# Flash_Memory.net
KiCad netlist of a schematic drawn in Altium Designer
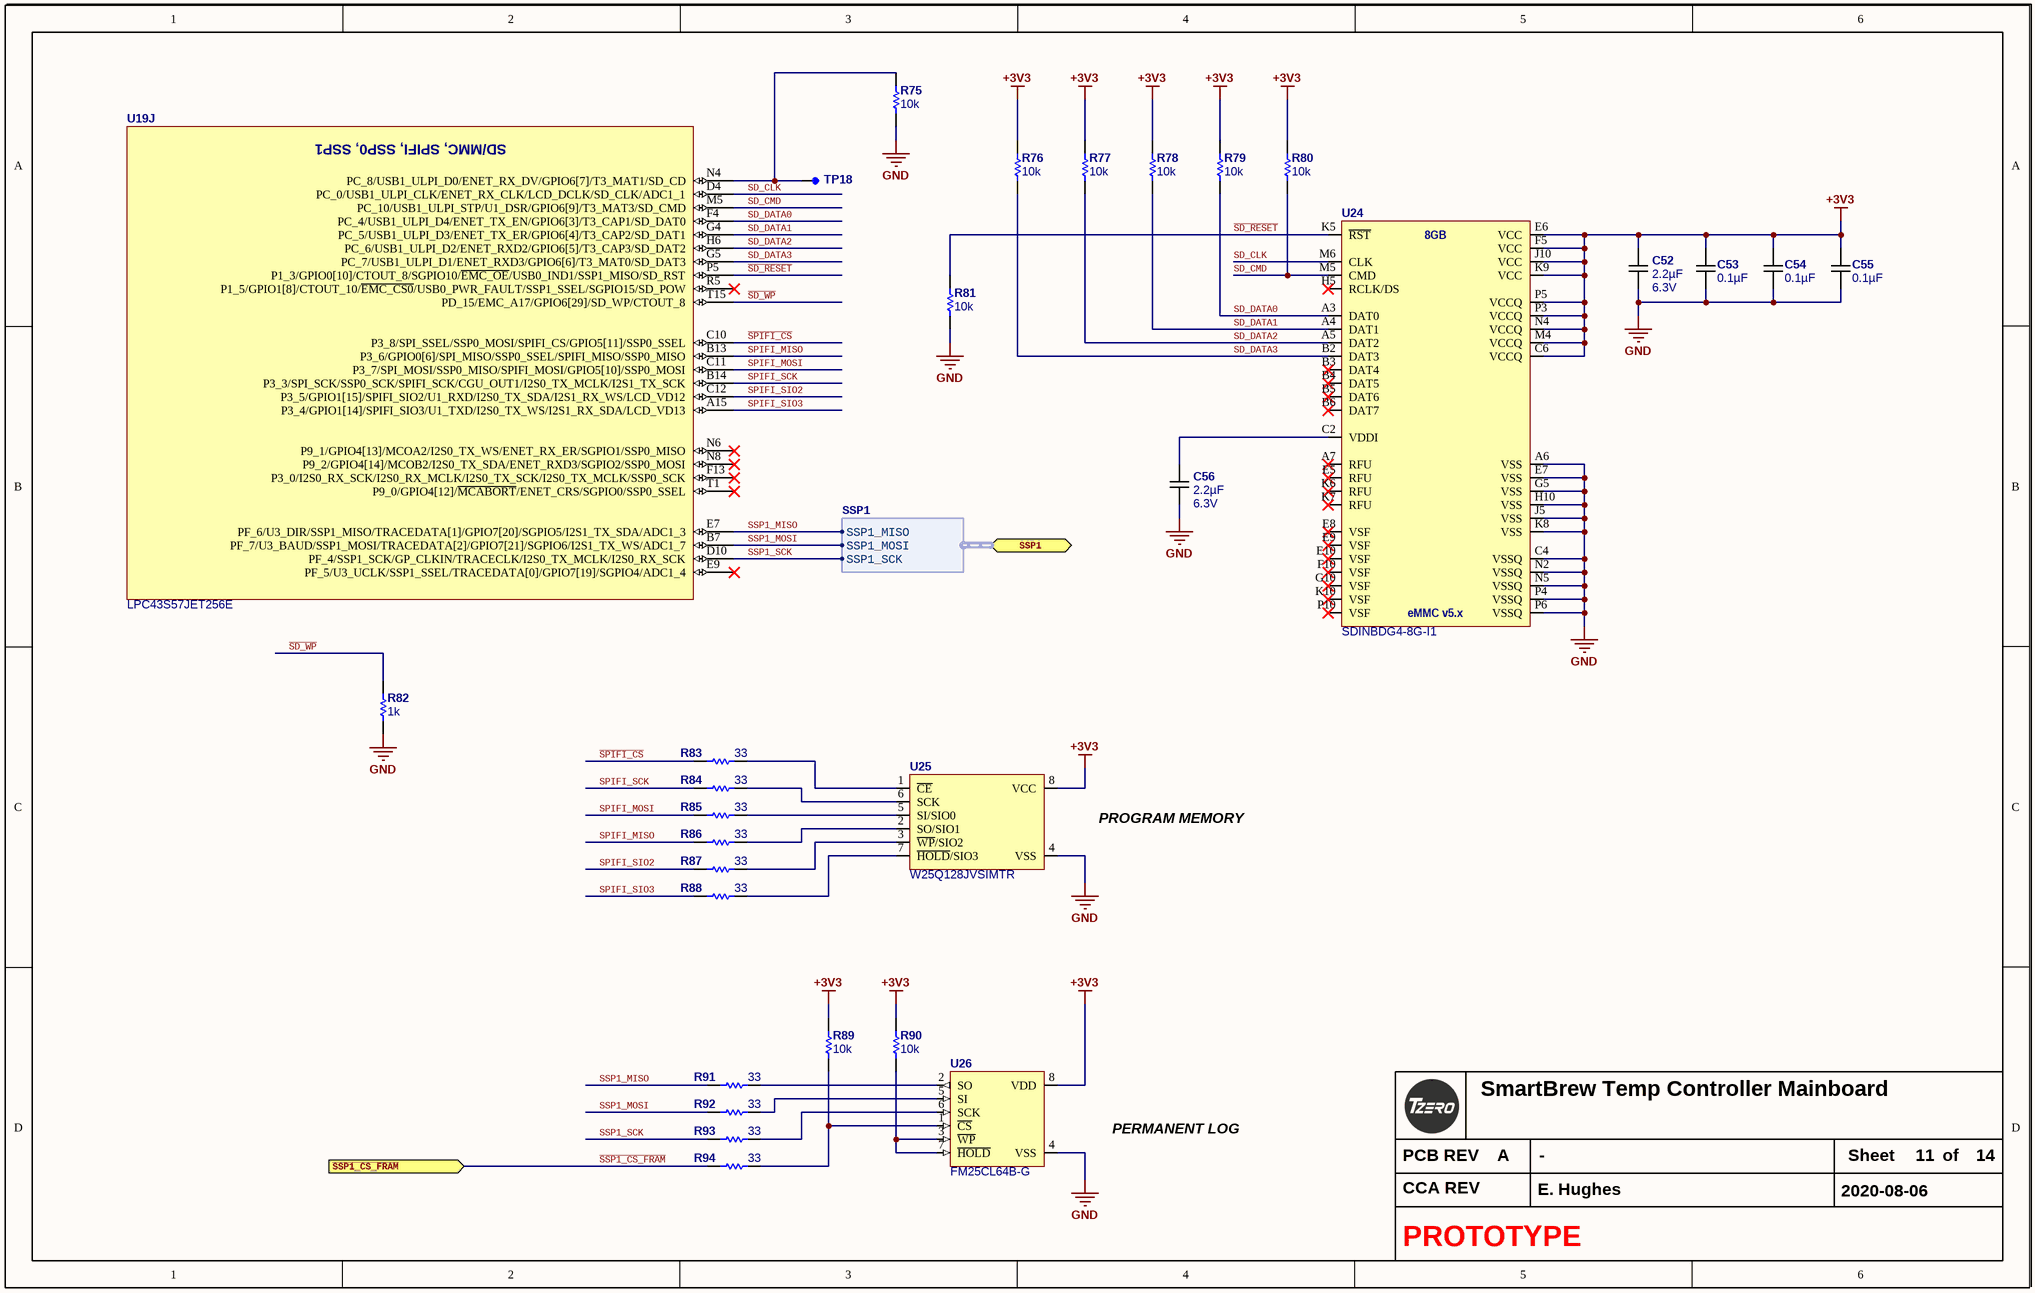
[diagram p0: Flash Memory.SchDoc]

(export (version "E")
  (design (tool "Eeschema 10.0.6"))
  (components
    (comp (ref "C52")
      (value "2.2µF")
      (footprint "C0603_0.90MM_HD")
      (description "CAP CER 2.2UF 6.3V X7R 0603")
      (fields
        (field (name "MANUFACTURER PART NUMBER") "CGA3E1X7R0J225M080AC")
        (field (name "MANUFACTURER") "TDK Corporation")
        (field (name "VOLTAGE - RATED") "6.3V")
      )
      (libsource (lib "Capacitors - TDK- AEC-Q200") (part "C_2P_NP"))
    )
    (comp (ref "C53")
      (value "0.1µF")
      (footprint "C0402_0.55MM_HD")
      (description "CAP CER 0.1UF 25V X7R 0402")
      (fields
        (field (name "MANUFACTURER PART NUMBER") "CGA2B3X7R1E104K050BB")
        (field (name "MANUFACTURER") "TDK Corporation")
      )
      (libsource (lib "Capacitors - TDK- AEC-Q200") (part "C_2P_NP"))
    )
    (comp (ref "C54")
      (value "0.1µF")
      (footprint "C0402_0.55MM_HD")
      (description "CAP CER 0.1UF 25V X7R 0402")
      (fields
        (field (name "MANUFACTURER PART NUMBER") "CGA2B3X7R1E104K050BB")
        (field (name "MANUFACTURER") "TDK Corporation")
      )
      (libsource (lib "Capacitors - TDK- AEC-Q200") (part "C_2P_NP"))
    )
    (comp (ref "C55")
      (value "0.1µF")
      (footprint "C0402_0.55MM_HD")
      (description "CAP CER 0.1UF 25V X7R 0402")
      (fields
        (field (name "MANUFACTURER PART NUMBER") "CGA2B3X7R1E104K050BB")
        (field (name "MANUFACTURER") "TDK Corporation")
      )
      (libsource (lib "Capacitors - TDK- AEC-Q200") (part "C_2P_NP"))
    )
    (comp (ref "C56")
      (value "2.2µF")
      (footprint "C0603_0.90MM_HD")
      (description "CAP CER 2.2UF 6.3V X7R 0603")
      (fields
        (field (name "MANUFACTURER PART NUMBER") "CGA3E1X7R0J225M080AC")
        (field (name "MANUFACTURER") "TDK Corporation")
        (field (name "VOLTAGE - RATED") "6.3V")
      )
      (libsource (lib "Capacitors - TDK- AEC-Q200") (part "C_2P_NP"))
    )
    (comp (ref "R75")
      (value "10k")
      (footprint "R0603_0.55MM_MD")
      (description "RES 10K OHM 1/10W 1% 0603 SMD")
      (fields
        (field (name "MANUFACTURER") "Panasonic Electronic Components")
        (field (name "MANUFACTURER PART NUMBER") "ERJ-3EKF1002V")
      )
      (libsource (lib "Resistors - Panasonic - AEC-Q200") (part "R_2P"))
    )
    (comp (ref "R76")
      (value "10k")
      (footprint "R0603_0.55MM_MD")
      (description "RES 10K OHM 1/10W 1% 0603 SMD")
      (fields
        (field (name "MANUFACTURER") "Panasonic Electronic Components")
        (field (name "MANUFACTURER PART NUMBER") "ERJ-3EKF1002V")
      )
      (libsource (lib "Resistors - Panasonic - AEC-Q200") (part "R_2P"))
    )
    (comp (ref "R77")
      (value "10k")
      (footprint "R0603_0.55MM_MD")
      (description "RES 10K OHM 1/10W 1% 0603 SMD")
      (fields
        (field (name "MANUFACTURER") "Panasonic Electronic Components")
        (field (name "MANUFACTURER PART NUMBER") "ERJ-3EKF1002V")
      )
      (libsource (lib "Resistors - Panasonic - AEC-Q200") (part "R_2P"))
    )
    (comp (ref "R78")
      (value "10k")
      (footprint "R0603_0.55MM_MD")
      (description "RES 10K OHM 1/10W 1% 0603 SMD")
      (fields
        (field (name "MANUFACTURER") "Panasonic Electronic Components")
        (field (name "MANUFACTURER PART NUMBER") "ERJ-3EKF1002V")
      )
      (libsource (lib "Resistors - Panasonic - AEC-Q200") (part "R_2P"))
    )
    (comp (ref "R79")
      (value "10k")
      (footprint "R0603_0.55MM_MD")
      (description "RES 10K OHM 1/10W 1% 0603 SMD")
      (fields
        (field (name "MANUFACTURER") "Panasonic Electronic Components")
        (field (name "MANUFACTURER PART NUMBER") "ERJ-3EKF1002V")
      )
      (libsource (lib "Resistors - Panasonic - AEC-Q200") (part "R_2P"))
    )
    (comp (ref "R80")
      (value "10k")
      (footprint "R0603_0.55MM_MD")
      (description "RES 10K OHM 1/10W 1% 0603 SMD")
      (fields
        (field (name "MANUFACTURER") "Panasonic Electronic Components")
        (field (name "MANUFACTURER PART NUMBER") "ERJ-3EKF1002V")
      )
      (libsource (lib "Resistors - Panasonic - AEC-Q200") (part "R_2P"))
    )
    (comp (ref "R81")
      (value "10k")
      (footprint "R0603_0.55MM_MD")
      (description "RES 10K OHM 1/10W 1% 0603 SMD")
      (fields
        (field (name "MANUFACTURER") "Panasonic Electronic Components")
        (field (name "MANUFACTURER PART NUMBER") "ERJ-3EKF1002V")
      )
      (libsource (lib "Resistors - Panasonic - AEC-Q200") (part "R_2P"))
    )
    (comp (ref "R82")
      (value "1k")
      (footprint "R0603_0.55MM_MD")
      (description "RES 1K OHM 1/10W 1% 0603 SMD")
      (fields
        (field (name "MANUFACTURER PART NUMBER") "ERJ-3EKF1001V")
        (field (name "MANUFACTURER") "Panasonic Electronic Components")
      )
      (libsource (lib "Resistors - Panasonic - AEC-Q200") (part "R_2P"))
    )
    (comp (ref "R83")
      (value "33")
      (footprint "R0603_0.55MM_MD")
      (description "RES 33 OHM 1/10W 1% 0603 SMD")
      (fields
        (field (name "MANUFACTURER") "Panasonic Electronic Components")
        (field (name "MANUFACTURER PART NUMBER") "ERJ-3EKF33R0V")
      )
      (libsource (lib "Resistors - Panasonic - AEC-Q200") (part "R_2P"))
    )
    (comp (ref "R84")
      (value "33")
      (footprint "R0603_0.55MM_MD")
      (description "RES 33 OHM 1/10W 1% 0603 SMD")
      (fields
        (field (name "MANUFACTURER") "Panasonic Electronic Components")
        (field (name "MANUFACTURER PART NUMBER") "ERJ-3EKF33R0V")
      )
      (libsource (lib "Resistors - Panasonic - AEC-Q200") (part "R_2P"))
    )
    (comp (ref "R85")
      (value "33")
      (footprint "R0603_0.55MM_MD")
      (description "RES 33 OHM 1/10W 1% 0603 SMD")
      (fields
        (field (name "MANUFACTURER") "Panasonic Electronic Components")
        (field (name "MANUFACTURER PART NUMBER") "ERJ-3EKF33R0V")
      )
      (libsource (lib "Resistors - Panasonic - AEC-Q200") (part "R_2P"))
    )
    (comp (ref "R86")
      (value "33")
      (footprint "R0603_0.55MM_MD")
      (description "RES 33 OHM 1/10W 1% 0603 SMD")
      (fields
        (field (name "MANUFACTURER") "Panasonic Electronic Components")
        (field (name "MANUFACTURER PART NUMBER") "ERJ-3EKF33R0V")
      )
      (libsource (lib "Resistors - Panasonic - AEC-Q200") (part "R_2P"))
    )
    (comp (ref "R87")
      (value "33")
      (footprint "R0603_0.55MM_MD")
      (description "RES 33 OHM 1/10W 1% 0603 SMD")
      (fields
        (field (name "MANUFACTURER") "Panasonic Electronic Components")
        (field (name "MANUFACTURER PART NUMBER") "ERJ-3EKF33R0V")
      )
      (libsource (lib "Resistors - Panasonic - AEC-Q200") (part "R_2P"))
    )
    (comp (ref "R88")
      (value "33")
      (footprint "R0603_0.55MM_MD")
      (description "RES 33 OHM 1/10W 1% 0603 SMD")
      (fields
        (field (name "MANUFACTURER") "Panasonic Electronic Components")
        (field (name "MANUFACTURER PART NUMBER") "ERJ-3EKF33R0V")
      )
      (libsource (lib "Resistors - Panasonic - AEC-Q200") (part "R_2P"))
    )
    (comp (ref "R89")
      (value "10k")
      (footprint "R0603_0.55MM_MD")
      (description "RES 10K OHM 1/10W 1% 0603 SMD")
      (fields
        (field (name "MANUFACTURER") "Panasonic Electronic Components")
        (field (name "MANUFACTURER PART NUMBER") "ERJ-3EKF1002V")
      )
      (libsource (lib "Resistors - Panasonic - AEC-Q200") (part "R_2P"))
    )
    (comp (ref "R90")
      (value "10k")
      (footprint "R0603_0.55MM_MD")
      (description "RES 10K OHM 1/10W 1% 0603 SMD")
      (fields
        (field (name "MANUFACTURER") "Panasonic Electronic Components")
        (field (name "MANUFACTURER PART NUMBER") "ERJ-3EKF1002V")
      )
      (libsource (lib "Resistors - Panasonic - AEC-Q200") (part "R_2P"))
    )
    (comp (ref "R91")
      (value "33")
      (footprint "R0603_0.55MM_MD")
      (description "RES 33 OHM 1/10W 1% 0603 SMD")
      (fields
        (field (name "MANUFACTURER") "Panasonic Electronic Components")
        (field (name "MANUFACTURER PART NUMBER") "ERJ-3EKF33R0V")
      )
      (libsource (lib "Resistors - Panasonic - AEC-Q200") (part "R_2P"))
    )
    (comp (ref "R92")
      (value "33")
      (footprint "R0603_0.55MM_MD")
      (description "RES 33 OHM 1/10W 1% 0603 SMD")
      (fields
        (field (name "MANUFACTURER") "Panasonic Electronic Components")
        (field (name "MANUFACTURER PART NUMBER") "ERJ-3EKF33R0V")
      )
      (libsource (lib "Resistors - Panasonic - AEC-Q200") (part "R_2P"))
    )
    (comp (ref "R93")
      (value "33")
      (footprint "R0603_0.55MM_MD")
      (description "RES 33 OHM 1/10W 1% 0603 SMD")
      (fields
        (field (name "MANUFACTURER") "Panasonic Electronic Components")
        (field (name "MANUFACTURER PART NUMBER") "ERJ-3EKF33R0V")
      )
      (libsource (lib "Resistors - Panasonic - AEC-Q200") (part "R_2P"))
    )
    (comp (ref "R94")
      (value "33")
      (footprint "R0603_0.55MM_MD")
      (description "RES 33 OHM 1/10W 1% 0603 SMD")
      (fields
        (field (name "MANUFACTURER") "Panasonic Electronic Components")
        (field (name "MANUFACTURER PART NUMBER") "ERJ-3EKF33R0V")
      )
      (libsource (lib "Resistors - Panasonic - AEC-Q200") (part "R_2P"))
    )
    (comp (ref "TP18")
      (value "~")
      (footprint "TP_SMT_25_MIL_ROUND")
      (libsource (lib "Test Points-N") (part "TP SMT 25MIL"))
    )
    (comp (ref "U19")
      (value "LPC43S57JET256E")
      (footprint "Integrated Circuits BGA-N:LBGA256 16X16 1700X1700X155")
      (description "ARM Microcontrollers - MCU CortexM0/4 32bit 1MB Cortex-M4/M0")
      (fields (field (name "MANUFACTURER") "NXP Semiconductors"))
      (libsource (lib "eIC") (part "LPC43S57JET256E"))
    )
    (comp (ref "U24")
      (value "SDINBDG4-8G-I1")
      (footprint "BGA_JDEC_EMMC_11.5x13.1x1.1_153PIN")
      (description "eMMC eMMC seq 300/40 IOPs 7800/8000")
      (fields (field (name "MANUFACTURER") "SanDisk"))
      (libsource (lib "Memory-N") (part "SDINBDG4-8G-I1"))
    )
    (comp (ref "U25")
      (value "W25Q128JVSIMTR")
      (footprint "SOIC-8W")
      (description "IC FLASH 128M SPI 133MHZ 8SOIC")
      (fields (field (name "MANUFACTURER") "Winbond"))
      (libsource (lib "Memory-N") (part "W25Q128JVSIMTR"))
    )
    (comp (ref "U26")
      (value "FM25CL64B-G")
      (footprint "SOIC-8")
      (description "IC FRAM 64K SPI 20MHZ 8SOIC")
      (fields (field (name "MANUFACTURER") "Cypress"))
      (libsource (lib "Memory-N") (part "FM25CL64B-G"))
    )
  )
  (nets
    (net (code "2") (name "+3V3") (class "Default")
      (node (ref "C52") (pin "2") (pinfunction "1_2") (pintype "passive"))
      (node (ref "C53") (pin "2") (pinfunction "1_2") (pintype "passive"))
      (node (ref "C54") (pin "2") (pinfunction "1_2") (pintype "passive"))
      (node (ref "C55") (pin "2") (pinfunction "1_2") (pintype "passive"))
      (node (ref "R76") (pin "2") (pinfunction "2_2") (pintype "passive"))
      (node (ref "R77") (pin "2") (pinfunction "2_2") (pintype "passive"))
      (node (ref "R78") (pin "2") (pinfunction "2_2") (pintype "passive"))
      (node (ref "R79") (pin "2") (pinfunction "2_2") (pintype "passive"))
      (node (ref "R80") (pin "2") (pinfunction "2_2") (pintype "passive"))
      (node (ref "R89") (pin "1") (pinfunction "1_1") (pintype "passive"))
      (node (ref "R90") (pin "2") (pinfunction "2_2") (pintype "passive"))
      (node (ref "U24") (pin "C6") (pinfunction "VCCQ_C6") (pintype "passive"))
      (node (ref "U24") (pin "E6") (pinfunction "VCC_E6") (pintype "passive"))
      (node (ref "U24") (pin "F5") (pinfunction "VCC_F5") (pintype "passive"))
      (node (ref "U24") (pin "J10") (pinfunction "VCC_J10") (pintype "passive"))
      (node (ref "U24") (pin "K9") (pinfunction "VCC_K9") (pintype "passive"))
      (node (ref "U24") (pin "M4") (pinfunction "VCCQ_M4") (pintype "passive"))
      (node (ref "U24") (pin "N4") (pinfunction "VCCQ_N4") (pintype "passive"))
      (node (ref "U24") (pin "P3") (pinfunction "VCCQ_P3") (pintype "passive"))
      (node (ref "U24") (pin "P5") (pinfunction "VCCQ_P5") (pintype "passive"))
      (node (ref "U25") (pin "8") (pinfunction "VCC_8") (pintype "passive"))
      (node (ref "U26") (pin "8") (pinfunction "VDD_8") (pintype "power_in"))
    )
    (net (code "3") (name "/SD_CLK") (class "Default")
      (node (ref "U19") (pin "D4") (pinfunction "PC_0/USB1_ULPI_CLK/ENET_RX_CLK/LCD_DCLK/SD_CLK/ADC1_1_D4") (pintype "bidirectional"))
      (node (ref "U24") (pin "M6") (pinfunction "CLK_M6") (pintype "passive"))
    )
    (net (code "4") (name "/SD_CMD") (class "Default")
      (node (ref "R80") (pin "1") (pinfunction "1_1") (pintype "passive"))
      (node (ref "U19") (pin "M5") (pinfunction "PC_10/USB1_ULPI_STP/U1_DSR/GPIO6[9]/T3_MAT3/SD_CMD_M5") (pintype "bidirectional"))
      (node (ref "U24") (pin "M5") (pinfunction "CMD_M5") (pintype "passive"))
    )
    (net (code "5") (name "/SD_DATA0") (class "Default")
      (node (ref "R79") (pin "1") (pinfunction "1_1") (pintype "passive"))
      (node (ref "U19") (pin "F4") (pinfunction "PC_4/USB1_ULPI_D4/ENET_TX_EN/GPIO6[3]/T3_CAP1/SD_DAT0_F4") (pintype "bidirectional"))
      (node (ref "U24") (pin "A3") (pinfunction "DAT0_A3") (pintype "passive"))
    )
    (net (code "6") (name "/SD_DATA1") (class "Default")
      (node (ref "R78") (pin "1") (pinfunction "1_1") (pintype "passive"))
      (node (ref "U19") (pin "G4") (pinfunction "PC_5/USB1_ULPI_D3/ENET_TX_ER/GPIO6[4]/T3_CAP2/SD_DAT1_G4") (pintype "bidirectional"))
      (node (ref "U24") (pin "A4") (pinfunction "DAT1_A4") (pintype "passive"))
    )
    (net (code "7") (name "/SD_DATA2") (class "Default")
      (node (ref "R77") (pin "1") (pinfunction "1_1") (pintype "passive"))
      (node (ref "U19") (pin "H6") (pinfunction "PC_6/USB1_ULPI_D2/ENET_RXD2/GPIO6[5]/T3_CAP3/SD_DAT2_H6") (pintype "bidirectional"))
      (node (ref "U24") (pin "A5") (pinfunction "DAT2_A5") (pintype "passive"))
    )
    (net (code "8") (name "/SD_DATA3") (class "Default")
      (node (ref "R76") (pin "1") (pinfunction "1_1") (pintype "passive"))
      (node (ref "U19") (pin "G5") (pinfunction "PC_7/USB1_ULPI_D1/ENET_RXD3/GPIO6[6]/T3_MAT0/SD_DAT3_G5") (pintype "bidirectional"))
      (node (ref "U24") (pin "B2") (pinfunction "DAT3_B2") (pintype "passive"))
    )
    (net (code "9") (name "/SD_RESET") (class "Default")
      (node (ref "R81") (pin "2") (pinfunction "2_2") (pintype "passive"))
      (node (ref "U19") (pin "P5") (pinfunction "P1_3/GPIO0[10]/CTOUT_8/SGPIO10/~{EMC_OE}/USB0_IND1/SSP1_MISO/SD_RST_P5") (pintype "bidirectional"))
      (node (ref "U24") (pin "K5") (pinfunction "RST_K5") (pintype "passive"))
    )
    (net (code "10") (name "/SD_WP") (class "Default")
      (node (ref "R82") (pin "2") (pinfunction "2_2") (pintype "passive"))
      (node (ref "U19") (pin "T15") (pinfunction "PD_15/EMC_A17/GPIO6[29]/SD_WP/CTOUT_8_T15") (pintype "bidirectional"))
    )
    (net (code "11") (name "/SPIFI_CS") (class "Default")
      (node (ref "R83") (pin "2") (pinfunction "2_2") (pintype "passive"))
      (node (ref "U19") (pin "C10") (pinfunction "P3_8/SPI_SSEL/SSP0_MOSI/SPIFI_CS/GPIO5[11]/SSP0_SSEL_C10") (pintype "bidirectional"))
    )
    (net (code "12") (name "/SPIFI_MISO") (class "Default")
      (node (ref "R86") (pin "2") (pinfunction "2_2") (pintype "passive"))
      (node (ref "U19") (pin "B13") (pinfunction "P3_6/GPIO0[6]/SPI_MISO/SSP0_SSEL/SPIFI_MISO/SSP0_MISO_B13") (pintype "bidirectional"))
    )
    (net (code "13") (name "/SPIFI_MOSI") (class "Default")
      (node (ref "R85") (pin "2") (pinfunction "2_2") (pintype "passive"))
      (node (ref "U19") (pin "C11") (pinfunction "P3_7/SPI_MOSI/SSP0_MISO/SPIFI_MOSI/GPIO5[10]/SSP0_MOSI_C11") (pintype "bidirectional"))
    )
    (net (code "14") (name "/SPIFI_SCK") (class "Default")
      (node (ref "R84") (pin "2") (pinfunction "2_2") (pintype "passive"))
      (node (ref "U19") (pin "B14") (pinfunction "P3_3/SPI_SCK/SSP0_SCK/SPIFI_SCK/CGU_OUT1/I2S0_TX_MCLK/I2S1_TX_SCK_B14") (pintype "bidirectional"))
    )
    (net (code "15") (name "/SPIFI_SIO2") (class "Default")
      (node (ref "R87") (pin "2") (pinfunction "2_2") (pintype "passive"))
      (node (ref "U19") (pin "C12") (pinfunction "P3_5/GPIO1[15]/SPIFI_SIO2/U1_RXD/I2S0_TX_SDA/I2S1_RX_WS/LCD_VD12_C12") (pintype "bidirectional"))
    )
    (net (code "16") (name "/SPIFI_SIO3") (class "Default")
      (node (ref "R88") (pin "2") (pinfunction "2_2") (pintype "passive"))
      (node (ref "U19") (pin "A15") (pinfunction "P3_4/GPIO1[14]/SPIFI_SIO3/U1_TXD/I2S0_TX_WS/I2S1_RX_SDA/LCD_VD13_A15") (pintype "bidirectional"))
    )
    (net (code "17") (name "/SSP1_CS_FRAM") (class "Default")
      (node (ref "R94") (pin "2") (pinfunction "2_2") (pintype "passive"))
    )
    (net (code "18") (name "/SSP1_MISO") (class "Default")
      (node (ref "R91") (pin "2") (pinfunction "2_2") (pintype "passive"))
      (node (ref "U19") (pin "E7") (pinfunction "PF_6/U3_DIR/SSP1_MISO/TRACEDATA[1]/GPIO7[20]/SGPIO5/I2S1_TX_SDA/ADC1_3_E7") (pintype "bidirectional"))
    )
    (net (code "19") (name "/SSP1_MOSI") (class "Default")
      (node (ref "R92") (pin "2") (pinfunction "2_2") (pintype "passive"))
      (node (ref "U19") (pin "B7") (pinfunction "PF_7/U3_BAUD/SSP1_MOSI/TRACEDATA[2]/GPIO7[21]/SGPIO6/I2S1_TX_WS/ADC1_7_B7") (pintype "bidirectional"))
    )
    (net (code "20") (name "/SSP1_SCK") (class "Default")
      (node (ref "R93") (pin "2") (pinfunction "2_2") (pintype "passive"))
      (node (ref "U19") (pin "D10") (pinfunction "PF_4/SSP1_SCK/GP_CLKIN/TRACECLK/I2S0_TX_MCLK/I2S0_RX_SCK_D10") (pintype "bidirectional"))
    )
    (net (code "22") (name "GND") (class "Default")
      (node (ref "C52") (pin "1") (pinfunction "1_1") (pintype "passive"))
      (node (ref "C53") (pin "1") (pinfunction "1_1") (pintype "passive"))
      (node (ref "C54") (pin "1") (pinfunction "1_1") (pintype "passive"))
      (node (ref "C55") (pin "1") (pinfunction "1_1") (pintype "passive"))
      (node (ref "C56") (pin "1") (pinfunction "1_1") (pintype "passive"))
      (node (ref "R75") (pin "1") (pinfunction "1_1") (pintype "passive"))
      (node (ref "R81") (pin "1") (pinfunction "1_1") (pintype "passive"))
      (node (ref "R82") (pin "1") (pinfunction "1_1") (pintype "passive"))
      (node (ref "U24") (pin "A6") (pinfunction "VSS_A6") (pintype "passive"))
      (node (ref "U24") (pin "C4") (pinfunction "VSSQ_C4") (pintype "passive"))
      (node (ref "U24") (pin "E7") (pinfunction "VSS_E7") (pintype "passive"))
      (node (ref "U24") (pin "G5") (pinfunction "VSS_G5") (pintype "passive"))
      (node (ref "U24") (pin "H10") (pinfunction "VSS_H10") (pintype "passive"))
      (node (ref "U24") (pin "J5") (pinfunction "VSS_J5") (pintype "passive"))
      (node (ref "U24") (pin "K8") (pinfunction "VSS_K8") (pintype "passive"))
      (node (ref "U24") (pin "N2") (pinfunction "VSSQ_N2") (pintype "passive"))
      (node (ref "U24") (pin "N5") (pinfunction "VSSQ_N5") (pintype "passive"))
      (node (ref "U24") (pin "P4") (pinfunction "VSSQ_P4") (pintype "passive"))
      (node (ref "U24") (pin "P6") (pinfunction "VSSQ_P6") (pintype "passive"))
      (node (ref "U25") (pin "4") (pinfunction "VSS_4") (pintype "passive"))
      (node (ref "U26") (pin "4") (pinfunction "VSS_4") (pintype "power_in"))
    )
    (net (code "23") (name "Net-(U19J-PC_8{slash}USB1_ULPI_D0{slash}ENET_RX_DV{slash}GPIO6[7]{slash}T3_MAT1{slash}SD_CD)") (class "Default")
      (node (ref "R75") (pin "2") (pinfunction "2_2") (pintype "passive"))
      (node (ref "TP18") (pin "1") (pinfunction "1_1") (pintype "passive"))
      (node (ref "U19") (pin "N4") (pinfunction "PC_8/USB1_ULPI_D0/ENET_RX_DV/GPIO6[7]/T3_MAT1/SD_CD_N4") (pintype "bidirectional"))
    )
    (net (code "24") (name "Net-(U24-VDDI)") (class "Default")
      (node (ref "C56") (pin "2") (pinfunction "1_2") (pintype "passive"))
      (node (ref "U24") (pin "C2") (pinfunction "VDDI_C2") (pintype "passive"))
    )
    (net (code "25") (name "Net-(U25-CE)") (class "Default")
      (node (ref "R83") (pin "1") (pinfunction "1_1") (pintype "passive"))
      (node (ref "U25") (pin "1") (pinfunction "CE_1") (pintype "passive"))
    )
    (net (code "26") (name "Net-(U25-SCK)") (class "Default")
      (node (ref "R84") (pin "1") (pinfunction "1_1") (pintype "passive"))
      (node (ref "U25") (pin "6") (pinfunction "SCK_6") (pintype "passive"))
    )
    (net (code "27") (name "Net-(U25-SI{slash}SIO0)") (class "Default")
      (node (ref "R85") (pin "1") (pinfunction "1_1") (pintype "passive"))
      (node (ref "U25") (pin "5") (pinfunction "SI/SIO0_5") (pintype "passive"))
    )
    (net (code "28") (name "Net-(U25-SO{slash}SIO1)") (class "Default")
      (node (ref "R86") (pin "1") (pinfunction "1_1") (pintype "passive"))
      (node (ref "U25") (pin "2") (pinfunction "SO/SIO1_2") (pintype "passive"))
    )
    (net (code "29") (name "Net-(U25-~{HOLD}{slash}SIO3)") (class "Default")
      (node (ref "R88") (pin "1") (pinfunction "1_1") (pintype "passive"))
      (node (ref "U25") (pin "7") (pinfunction "~{HOLD}/SIO3_7") (pintype "passive"))
    )
    (net (code "30") (name "Net-(U25-~{WP}{slash}SIO2)") (class "Default")
      (node (ref "R87") (pin "1") (pinfunction "1_1") (pintype "passive"))
      (node (ref "U25") (pin "3") (pinfunction "~{WP}/SIO2_3") (pintype "passive"))
    )
    (net (code "31") (name "Net-(U26-CS)") (class "Default")
      (node (ref "R89") (pin "2") (pinfunction "2_2") (pintype "passive"))
      (node (ref "R94") (pin "1") (pinfunction "1_1") (pintype "passive"))
      (node (ref "U26") (pin "1") (pinfunction "CS_1") (pintype "input"))
    )
    (net (code "32") (name "Net-(U26-HOLD)") (class "Default")
      (node (ref "R90") (pin "1") (pinfunction "1_1") (pintype "passive"))
      (node (ref "U26") (pin "3") (pinfunction "WP_3") (pintype "input"))
      (node (ref "U26") (pin "7") (pinfunction "HOLD_7") (pintype "input"))
    )
    (net (code "33") (name "Net-(U26-SCK)") (class "Default")
      (node (ref "R93") (pin "1") (pinfunction "1_1") (pintype "passive"))
      (node (ref "U26") (pin "6") (pinfunction "SCK_6") (pintype "input"))
    )
    (net (code "34") (name "Net-(U26-SI)") (class "Default")
      (node (ref "R92") (pin "1") (pinfunction "1_1") (pintype "passive"))
      (node (ref "U26") (pin "5") (pinfunction "SI_5") (pintype "input"))
    )
    (net (code "35") (name "Net-(U26-SO)") (class "Default")
      (node (ref "R91") (pin "1") (pinfunction "1_1") (pintype "passive"))
      (node (ref "U26") (pin "2") (pinfunction "SO_2") (pintype "output"))
    )
    (net (code "36") (name "unconnected-(U19J-P1_5{slash}GPIO1[8]{slash}CTOUT_10{slash}~{EMC_CS0}{slash}USB0_PWR_FAULT{slash}SSP1_SSEL{slash}SGPIO15{slash}SD_POW-PadR5)") (class "Default")
      (node (ref "U19") (pin "R5") (pinfunction "P1_5/GPIO1[8]/CTOUT_10/~{EMC_CS0}/USB0_PWR_FAULT/SSP1_SSEL/SGPIO15/SD_POW_R5") (pintype "bidirectional+no_connect"))
    )
    (net (code "37") (name "unconnected-(U19J-P3_0{slash}I2S0_RX_SCK{slash}I2S0_RX_MCLK{slash}I2S0_TX_SCK{slash}I2S0_TX_MCLK{slash}SSP0_SCK-PadF13)") (class "Default")
      (node (ref "U19") (pin "F13") (pinfunction "P3_0/I2S0_RX_SCK/I2S0_RX_MCLK/I2S0_TX_SCK/I2S0_TX_MCLK/SSP0_SCK_F13") (pintype "bidirectional+no_connect"))
    )
    (net (code "38") (name "unconnected-(U19J-P9_0{slash}GPIO4[12]{slash}~{MCABORT}{slash}ENET_CRS{slash}SGPIO0{slash}SSP0_SSEL-PadT1)") (class "Default")
      (node (ref "U19") (pin "T1") (pinfunction "P9_0/GPIO4[12]/~{MCABORT}/ENET_CRS/SGPIO0/SSP0_SSEL_T1") (pintype "bidirectional+no_connect"))
    )
    (net (code "39") (name "unconnected-(U19J-P9_1{slash}GPIO4[13]{slash}MCOA2{slash}I2S0_TX_WS{slash}ENET_RX_ER{slash}SGPIO1{slash}SSP0_MISO-PadN6)") (class "Default")
      (node (ref "U19") (pin "N6") (pinfunction "P9_1/GPIO4[13]/MCOA2/I2S0_TX_WS/ENET_RX_ER/SGPIO1/SSP0_MISO_N6") (pintype "bidirectional+no_connect"))
    )
    (net (code "40") (name "unconnected-(U19J-P9_2{slash}GPIO4[14]{slash}MCOB2{slash}I2S0_TX_SDA{slash}ENET_RXD3{slash}SGPIO2{slash}SSP0_MOSI-PadN8)") (class "Default")
      (node (ref "U19") (pin "N8") (pinfunction "P9_2/GPIO4[14]/MCOB2/I2S0_TX_SDA/ENET_RXD3/SGPIO2/SSP0_MOSI_N8") (pintype "bidirectional+no_connect"))
    )
    (net (code "41") (name "unconnected-(U19J-PF_5{slash}U3_UCLK{slash}SSP1_SSEL{slash}TRACEDATA[0]{slash}GPIO7[19]{slash}SGPIO4{slash}ADC1_4-PadE9)") (class "Default")
      (node (ref "U19") (pin "E9") (pinfunction "PF_5/U3_UCLK/SSP1_SSEL/TRACEDATA[0]/GPIO7[19]/SGPIO4/ADC1_4_E9") (pintype "bidirectional+no_connect"))
    )
    (net (code "42") (name "unconnected-(U24-DAT4-PadB3)") (class "Default")
      (node (ref "U24") (pin "B3") (pinfunction "DAT4_B3") (pintype "passive+no_connect"))
    )
    (net (code "43") (name "unconnected-(U24-DAT5-PadB4)") (class "Default")
      (node (ref "U24") (pin "B4") (pinfunction "DAT5_B4") (pintype "passive+no_connect"))
    )
    (net (code "44") (name "unconnected-(U24-DAT6-PadB5)") (class "Default")
      (node (ref "U24") (pin "B5") (pinfunction "DAT6_B5") (pintype "passive+no_connect"))
    )
    (net (code "45") (name "unconnected-(U24-DAT7-PadB6)") (class "Default")
      (node (ref "U24") (pin "B6") (pinfunction "DAT7_B6") (pintype "passive+no_connect"))
    )
    (net (code "46") (name "unconnected-(U24-RCLK{slash}DS-PadH5)") (class "Default")
      (node (ref "U24") (pin "H5") (pinfunction "RCLK/DS_H5") (pintype "passive+no_connect"))
    )
    (net (code "47") (name "unconnected-(U24-RFU-PadA7)") (class "Default")
      (node (ref "U24") (pin "A7") (pinfunction "RFU_A7") (pintype "passive+no_connect"))
    )
    (net (code "48") (name "unconnected-(U24-RFU-PadE5)") (class "Default")
      (node (ref "U24") (pin "E5") (pinfunction "RFU_E5") (pintype "passive+no_connect"))
    )
    (net (code "49") (name "unconnected-(U24-RFU-PadK6)") (class "Default")
      (node (ref "U24") (pin "K6") (pinfunction "RFU_K6") (pintype "passive+no_connect"))
    )
    (net (code "50") (name "unconnected-(U24-RFU-PadK7)") (class "Default")
      (node (ref "U24") (pin "K7") (pinfunction "RFU_K7") (pintype "passive+no_connect"))
    )
    (net (code "51") (name "unconnected-(U24-VSF-PadE8)") (class "Default")
      (node (ref "U24") (pin "E8") (pinfunction "VSF_E8") (pintype "passive+no_connect"))
    )
    (net (code "52") (name "unconnected-(U24-VSF-PadE9)") (class "Default")
      (node (ref "U24") (pin "E9") (pinfunction "VSF_E9") (pintype "passive+no_connect"))
    )
    (net (code "53") (name "unconnected-(U24-VSF-PadE10)") (class "Default")
      (node (ref "U24") (pin "E10") (pinfunction "VSF_E10") (pintype "passive+no_connect"))
    )
    (net (code "54") (name "unconnected-(U24-VSF-PadF10)") (class "Default")
      (node (ref "U24") (pin "F10") (pinfunction "VSF_F10") (pintype "passive+no_connect"))
    )
    (net (code "55") (name "unconnected-(U24-VSF-PadG10)") (class "Default")
      (node (ref "U24") (pin "G10") (pinfunction "VSF_G10") (pintype "passive+no_connect"))
    )
    (net (code "56") (name "unconnected-(U24-VSF-PadK10)") (class "Default")
      (node (ref "U24") (pin "K10") (pinfunction "VSF_K10") (pintype "passive+no_connect"))
    )
    (net (code "57") (name "unconnected-(U24-VSF-PadP10)") (class "Default")
      (node (ref "U24") (pin "P10") (pinfunction "VSF_P10") (pintype "passive+no_connect"))
    )
  )
)
